# 02_I2C_V1-0.net
KiCad netlist of a schematic drawn in Altium Designer
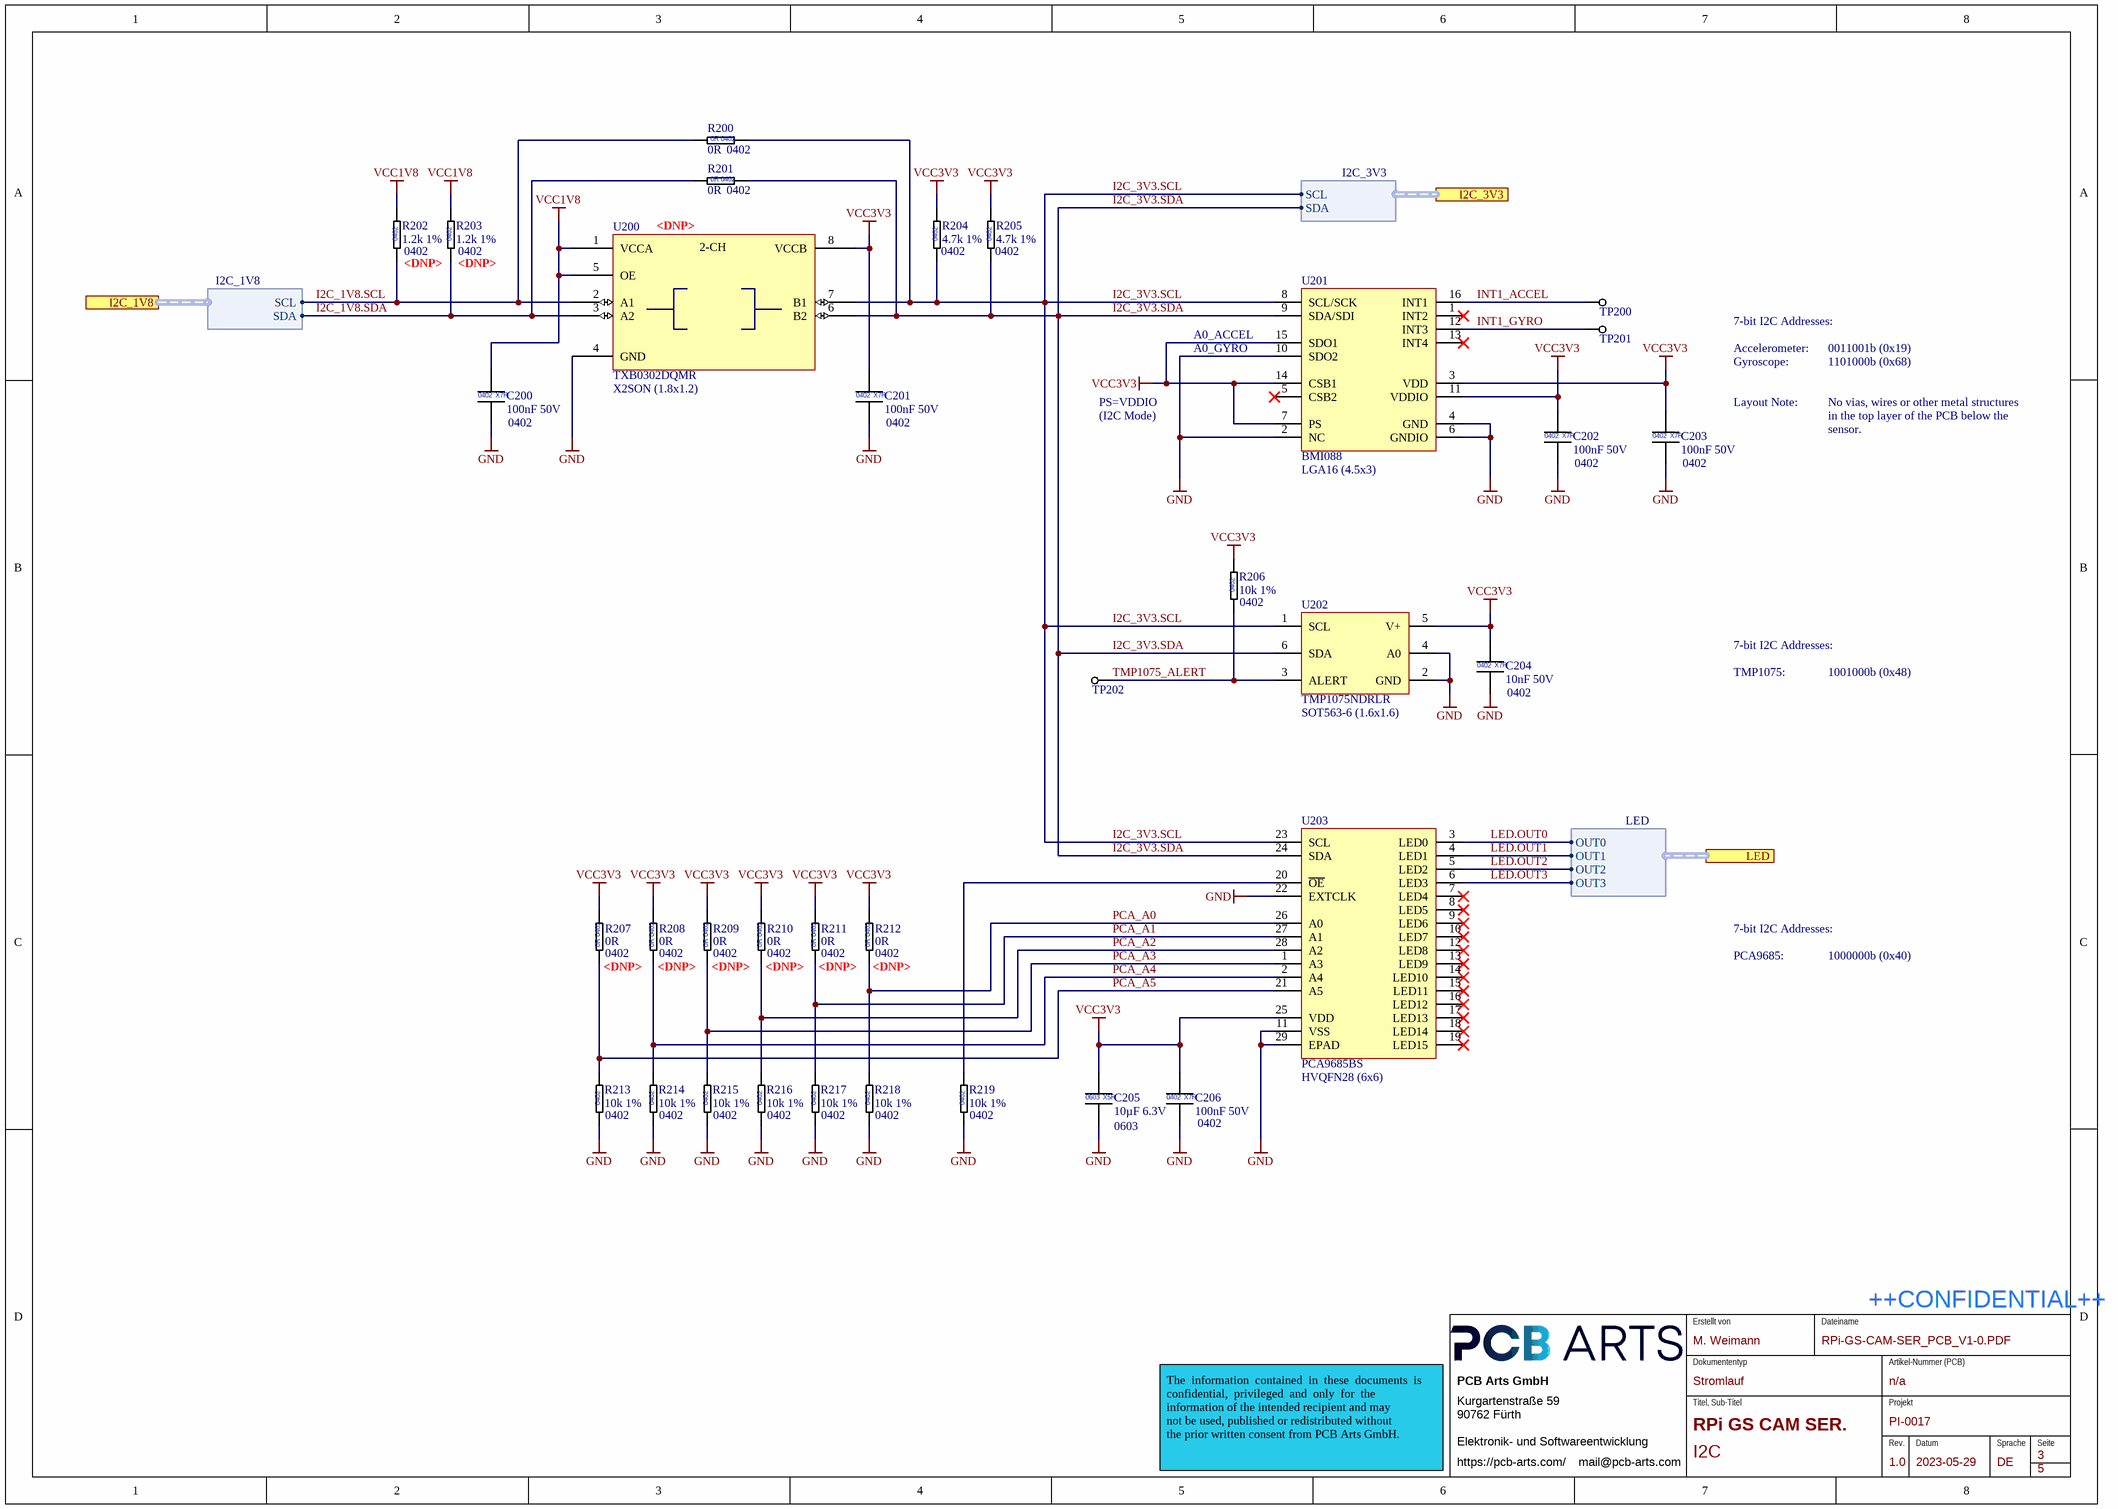
[diagram p0: 02_I2C_V1-0.SchDoc]

(export (version "E")
  (design (tool "Eeschema 10.0.6"))
  (components
    (comp (ref "C200")
      (value "100nF 50V")
      (footprint "Cap:CAP_0402_L")
      (description "Multilayer Ceramic Capacitors MLCC - SMD/SMT 0402 50VDC")
      (libsource (lib "Cap") (part "CAP_0402_100nF_50V"))
    )
    (comp (ref "C201")
      (value "100nF 50V")
      (footprint "Cap:CAP_0402_L")
      (description "Multilayer Ceramic Capacitors MLCC - SMD/SMT 0402 50VDC")
      (libsource (lib "Cap") (part "CAP_0402_100nF_50V"))
    )
    (comp (ref "C202")
      (value "100nF 50V")
      (footprint "Cap:CAP_0402_L")
      (description "Multilayer Ceramic Capacitors MLCC - SMD/SMT 0402 50VDC")
      (libsource (lib "Cap") (part "CAP_0402_100nF_50V"))
    )
    (comp (ref "C203")
      (value "100nF 50V")
      (footprint "Cap:CAP_0402_L")
      (description "Multilayer Ceramic Capacitors MLCC - SMD/SMT 0402 50VDC")
      (libsource (lib "Cap") (part "CAP_0402_100nF_50V"))
    )
    (comp (ref "C204")
      (value "10nF 50V")
      (footprint "Cap:CAP_0402_L")
      (description "Multilayer Ceramic Capacitors MLCC - SMD/SMT 0402 50VDC")
      (libsource (lib "Cap") (part "CAP_0402_10nF_50V"))
    )
    (comp (ref "C205")
      (value "10µF 6.3V")
      (footprint "Cap:CAP_0603_L")
      (description "Multilayer Ceramic Capacitors MLCC - SMD/SMT 0603 6.3VDC")
      (libsource (lib "Cap") (part "CAP_0603_10µF_6.3V"))
    )
    (comp (ref "C206")
      (value "100nF 50V")
      (footprint "Cap:CAP_0402_L")
      (description "Multilayer Ceramic Capacitors MLCC - SMD/SMT 0402 50VDC")
      (libsource (lib "Cap") (part "CAP_0402_100nF_50V"))
    )
    (comp (ref "R200")
      (value "0R Jumper")
      (footprint "Res:RES_0402_L")
      (description "Thick Film Resistors - SMD 0Ohm")
      (libsource (lib "Res") (part "RES_0402_0R Jumper"))
    )
    (comp (ref "R201")
      (value "0R Jumper")
      (footprint "Res:RES_0402_L")
      (description "Thick Film Resistors - SMD 0Ohm")
      (libsource (lib "Res") (part "RES_0402_0R Jumper"))
    )
    (comp (ref "R202")
      (value "1.2k 1%")
      (footprint "Res:RES_0402_L")
      (description "Thick Film Resistors - SMD 1/16watt 1.2Kohms 1%")
      (libsource (lib "Res") (part "RES_0402_1.2k_1%"))
    )
    (comp (ref "R203")
      (value "1.2k 1%")
      (footprint "Res:RES_0402_L")
      (description "Thick Film Resistors - SMD 1/16watt 1.2Kohms 1%")
      (libsource (lib "Res") (part "RES_0402_1.2k_1%"))
    )
    (comp (ref "R204")
      (value "4.7k 1%")
      (footprint "Res:RES_0402_L")
      (description "Thick Film Resistors - SMD 4.7kOhm 1%")
      (libsource (lib "Res") (part "RES_0402_4.7k_1%"))
    )
    (comp (ref "R205")
      (value "4.7k 1%")
      (footprint "Res:RES_0402_L")
      (description "Thick Film Resistors - SMD 4.7kOhm 1%")
      (libsource (lib "Res") (part "RES_0402_4.7k_1%"))
    )
    (comp (ref "R206")
      (value "10k 1%")
      (footprint "Res:RES_0402_L")
      (description "Thick Film Resistors - SMD 10kOhm 1%")
      (libsource (lib "Res") (part "RES_0402_10k_1%"))
    )
    (comp (ref "R207")
      (value "0R Jumper")
      (footprint "Res:RES_0402_L")
      (description "Thick Film Resistors - SMD 0Ohm")
      (libsource (lib "Res") (part "RES_0402_0R Jumper"))
    )
    (comp (ref "R208")
      (value "0R Jumper")
      (footprint "Res:RES_0402_L")
      (description "Thick Film Resistors - SMD 0Ohm")
      (libsource (lib "Res") (part "RES_0402_0R Jumper"))
    )
    (comp (ref "R209")
      (value "0R Jumper")
      (footprint "Res:RES_0402_L")
      (description "Thick Film Resistors - SMD 0Ohm")
      (libsource (lib "Res") (part "RES_0402_0R Jumper"))
    )
    (comp (ref "R210")
      (value "0R Jumper")
      (footprint "Res:RES_0402_L")
      (description "Thick Film Resistors - SMD 0Ohm")
      (libsource (lib "Res") (part "RES_0402_0R Jumper"))
    )
    (comp (ref "R211")
      (value "0R Jumper")
      (footprint "Res:RES_0402_L")
      (description "Thick Film Resistors - SMD 0Ohm")
      (libsource (lib "Res") (part "RES_0402_0R Jumper"))
    )
    (comp (ref "R212")
      (value "0R Jumper")
      (footprint "Res:RES_0402_L")
      (description "Thick Film Resistors - SMD 0Ohm")
      (libsource (lib "Res") (part "RES_0402_0R Jumper"))
    )
    (comp (ref "R213")
      (value "10k 1%")
      (footprint "Res:RES_0402_L")
      (description "Thick Film Resistors - SMD 10kOhm 1%")
      (libsource (lib "Res") (part "RES_0402_10k_1%"))
    )
    (comp (ref "R214")
      (value "10k 1%")
      (footprint "Res:RES_0402_L")
      (description "Thick Film Resistors - SMD 10kOhm 1%")
      (libsource (lib "Res") (part "RES_0402_10k_1%"))
    )
    (comp (ref "R215")
      (value "10k 1%")
      (footprint "Res:RES_0402_L")
      (description "Thick Film Resistors - SMD 10kOhm 1%")
      (libsource (lib "Res") (part "RES_0402_10k_1%"))
    )
    (comp (ref "R216")
      (value "10k 1%")
      (footprint "Res:RES_0402_L")
      (description "Thick Film Resistors - SMD 10kOhm 1%")
      (libsource (lib "Res") (part "RES_0402_10k_1%"))
    )
    (comp (ref "R217")
      (value "10k 1%")
      (footprint "Res:RES_0402_L")
      (description "Thick Film Resistors - SMD 10kOhm 1%")
      (libsource (lib "Res") (part "RES_0402_10k_1%"))
    )
    (comp (ref "R218")
      (value "10k 1%")
      (footprint "Res:RES_0402_L")
      (description "Thick Film Resistors - SMD 10kOhm 1%")
      (libsource (lib "Res") (part "RES_0402_10k_1%"))
    )
    (comp (ref "R219")
      (value "10k 1%")
      (footprint "Res:RES_0402_L")
      (description "Thick Film Resistors - SMD 10kOhm 1%")
      (libsource (lib "Res") (part "RES_0402_10k_1%"))
    )
    (comp (ref "TP200")
      (value "Testpoint")
      (footprint "Electro_mech:Testpoint 0.8mm")
      (description "Testpoint 0.8mm")
      (libsource (lib "Electro_Mech") (part "Testpoint 0.8mm"))
    )
    (comp (ref "TP201")
      (value "Testpoint")
      (footprint "Electro_mech:Testpoint 0.8mm")
      (description "Testpoint 0.8mm")
      (libsource (lib "Electro_Mech") (part "Testpoint 0.8mm"))
    )
    (comp (ref "TP202")
      (value "Testpoint")
      (footprint "Electro_mech:Testpoint 0.8mm")
      (description "Testpoint 0.8mm")
      (libsource (lib "Electro_Mech") (part "Testpoint 0.8mm"))
    )
    (comp (ref "U200")
      (value "TXB0302DQMR")
      (footprint "Digital:SON40P120X40-8N")
      (description "Translation - Voltage Levels 2B Bidir Vltg-Level Translator")
      (libsource (lib "Digital") (part "TXB0302DQMR_Translation - Voltage Levels 2B Bidir Vltg-Level Translator"))
    )
    (comp (ref "U201")
      (value "BMI088")
      (footprint "LGA50P450X300X100-16N")
      (libsource (lib "Digital") (part "BMI088_High_Performance_Intertial_Measurement_Unit_(IMU)"))
    )
    (comp (ref "U202")
      (value "TMP1075NDRLR")
      (footprint "SOT50P160X60-6N_SOT563")
      (libsource (lib "Digital") (part "TMP1075NDRLR_Board_Mount_I2C_Temperature_Sensor"))
    )
    (comp (ref "U203")
      (value "PCA9685BS")
      (footprint "QFN65P600X600X100_HS-29N")
      (description "LED-Anzeigetreiber 16-CH 12-BIT PWM FM+ I2C-BUS LED CTRL HVQFN28 6 mm x 6 mm")
      (libsource (lib "Digital") (part "PCA9685BS_16-CH_12-BIT-PWM_I2C_LED-CTRL"))
    )
  )
  (nets
    (net (code "4") (name "/I2C_1V8.SCL") (class "Default")
      (node (ref "R200") (pin "1") (pinfunction "1_1") (pintype "passive"))
      (node (ref "R202") (pin "1") (pinfunction "1_1") (pintype "passive"))
      (node (ref "U200") (pin "2") (pinfunction "A1_2") (pintype "bidirectional"))
    )
    (net (code "5") (name "/I2C_1V8.SDA") (class "Default")
      (node (ref "R201") (pin "1") (pinfunction "1_1") (pintype "passive"))
      (node (ref "R203") (pin "1") (pinfunction "1_1") (pintype "passive"))
      (node (ref "U200") (pin "3") (pinfunction "A2_3") (pintype "bidirectional"))
    )
    (net (code "6") (name "/I2C_3V3.SCL") (class "Default")
      (node (ref "R200") (pin "2") (pinfunction "2_2") (pintype "passive"))
      (node (ref "R204") (pin "1") (pinfunction "1_1") (pintype "passive"))
      (node (ref "U200") (pin "7") (pinfunction "B1_7") (pintype "bidirectional"))
      (node (ref "U201") (pin "8") (pinfunction "SCL/SCK_8") (pintype "passive"))
      (node (ref "U202") (pin "1") (pinfunction "SCL_1") (pintype "passive"))
      (node (ref "U203") (pin "23") (pinfunction "SCL_23") (pintype "passive"))
    )
    (net (code "7") (name "/I2C_3V3.SDA") (class "Default")
      (node (ref "R201") (pin "2") (pinfunction "2_2") (pintype "passive"))
      (node (ref "R205") (pin "1") (pinfunction "1_1") (pintype "passive"))
      (node (ref "U200") (pin "6") (pinfunction "B2_6") (pintype "bidirectional"))
      (node (ref "U201") (pin "9") (pinfunction "SDA/SDI_9") (pintype "passive"))
      (node (ref "U202") (pin "6") (pinfunction "SDA_6") (pintype "passive"))
      (node (ref "U203") (pin "24") (pinfunction "SDA_24") (pintype "passive"))
    )
    (net (code "8") (name "/INT1_ACCEL") (class "Default")
      (node (ref "TP200") (pin "1") (pinfunction "GND_1") (pintype "passive"))
      (node (ref "U201") (pin "16") (pinfunction "INT1_16") (pintype "passive"))
    )
    (net (code "9") (name "/INT1_GYRO") (class "Default")
      (node (ref "TP201") (pin "1") (pinfunction "GND_1") (pintype "passive"))
      (node (ref "U201") (pin "12") (pinfunction "INT3_12") (pintype "passive"))
    )
    (net (code "10") (name "/LED.OUT0") (class "Default")
      (node (ref "U203") (pin "3") (pinfunction "LED0_3") (pintype "passive"))
    )
    (net (code "11") (name "/LED.OUT1") (class "Default")
      (node (ref "U203") (pin "4") (pinfunction "LED1_4") (pintype "passive"))
    )
    (net (code "12") (name "/LED.OUT2") (class "Default")
      (node (ref "U203") (pin "5") (pinfunction "LED2_5") (pintype "passive"))
    )
    (net (code "13") (name "/LED.OUT3") (class "Default")
      (node (ref "U203") (pin "6") (pinfunction "LED3_6") (pintype "passive"))
    )
    (net (code "14") (name "/PCA_A0") (class "Default")
      (node (ref "R212") (pin "1") (pinfunction "1_1") (pintype "passive"))
      (node (ref "R218") (pin "2") (pinfunction "2_2") (pintype "passive"))
      (node (ref "U203") (pin "26") (pinfunction "A0_26") (pintype "passive"))
    )
    (net (code "15") (name "/PCA_A1") (class "Default")
      (node (ref "R211") (pin "1") (pinfunction "1_1") (pintype "passive"))
      (node (ref "R217") (pin "2") (pinfunction "2_2") (pintype "passive"))
      (node (ref "U203") (pin "27") (pinfunction "A1_27") (pintype "passive"))
    )
    (net (code "16") (name "/PCA_A2") (class "Default")
      (node (ref "R210") (pin "1") (pinfunction "1_1") (pintype "passive"))
      (node (ref "R216") (pin "2") (pinfunction "2_2") (pintype "passive"))
      (node (ref "U203") (pin "28") (pinfunction "A2_28") (pintype "passive"))
    )
    (net (code "17") (name "/PCA_A3") (class "Default")
      (node (ref "R209") (pin "1") (pinfunction "1_1") (pintype "passive"))
      (node (ref "R215") (pin "2") (pinfunction "2_2") (pintype "passive"))
      (node (ref "U203") (pin "1") (pinfunction "A3_1") (pintype "passive"))
    )
    (net (code "18") (name "/PCA_A4") (class "Default")
      (node (ref "R208") (pin "1") (pinfunction "1_1") (pintype "passive"))
      (node (ref "R214") (pin "2") (pinfunction "2_2") (pintype "passive"))
      (node (ref "U203") (pin "2") (pinfunction "A4_2") (pintype "passive"))
    )
    (net (code "19") (name "/PCA_A5") (class "Default")
      (node (ref "R207") (pin "1") (pinfunction "1_1") (pintype "passive"))
      (node (ref "R213") (pin "2") (pinfunction "2_2") (pintype "passive"))
      (node (ref "U203") (pin "21") (pinfunction "A5_21") (pintype "passive"))
    )
    (net (code "20") (name "/TMP1075_ALERT") (class "Default")
      (node (ref "R206") (pin "1") (pinfunction "1_1") (pintype "passive"))
      (node (ref "TP202") (pin "1") (pinfunction "GND_1") (pintype "passive"))
      (node (ref "U202") (pin "3") (pinfunction "ALERT_3") (pintype "passive"))
    )
    (net (code "24") (name "GND") (class "Default")
      (node (ref "C200") (pin "2") (pinfunction "2_2") (pintype "passive"))
      (node (ref "C201") (pin "2") (pinfunction "2_2") (pintype "passive"))
      (node (ref "C202") (pin "2") (pinfunction "2_2") (pintype "passive"))
      (node (ref "C203") (pin "2") (pinfunction "2_2") (pintype "passive"))
      (node (ref "C204") (pin "2") (pinfunction "2_2") (pintype "passive"))
      (node (ref "C205") (pin "2") (pinfunction "2_2") (pintype "passive"))
      (node (ref "C206") (pin "2") (pinfunction "2_2") (pintype "passive"))
      (node (ref "R213") (pin "1") (pinfunction "1_1") (pintype "passive"))
      (node (ref "R214") (pin "1") (pinfunction "1_1") (pintype "passive"))
      (node (ref "R215") (pin "1") (pinfunction "1_1") (pintype "passive"))
      (node (ref "R216") (pin "1") (pinfunction "1_1") (pintype "passive"))
      (node (ref "R217") (pin "1") (pinfunction "1_1") (pintype "passive"))
      (node (ref "R218") (pin "1") (pinfunction "1_1") (pintype "passive"))
      (node (ref "R219") (pin "1") (pinfunction "1_1") (pintype "passive"))
      (node (ref "U200") (pin "4") (pinfunction "GND_4") (pintype "power_in"))
      (node (ref "U201") (pin "10") (pinfunction "SDO2_10") (pintype "passive"))
      (node (ref "U201") (pin "2") (pinfunction "NC_2") (pintype "passive"))
      (node (ref "U201") (pin "4") (pinfunction "GND_4") (pintype "passive"))
      (node (ref "U201") (pin "6") (pinfunction "GNDIO_6") (pintype "passive"))
      (node (ref "U202") (pin "2") (pinfunction "GND_2") (pintype "passive"))
      (node (ref "U202") (pin "4") (pinfunction "A0_4") (pintype "passive"))
      (node (ref "U203") (pin "11") (pinfunction "VSS_11") (pintype "passive"))
      (node (ref "U203") (pin "22") (pinfunction "EXTCLK_22") (pintype "passive"))
      (node (ref "U203") (pin "29") (pinfunction "EPAD_29") (pintype "passive"))
    )
    (net (code "25") (name "Net-(U203-~{OE})") (class "Default")
      (node (ref "R219") (pin "2") (pinfunction "2_2") (pintype "passive"))
      (node (ref "U203") (pin "20") (pinfunction "~{OE}_20") (pintype "passive"))
    )
    (net (code "26") (name "VCC1V8") (class "Default")
      (node (ref "C200") (pin "1") (pinfunction "1_1") (pintype "passive"))
      (node (ref "R202") (pin "2") (pinfunction "2_2") (pintype "passive"))
      (node (ref "R203") (pin "2") (pinfunction "2_2") (pintype "passive"))
      (node (ref "U200") (pin "1") (pinfunction "VCCA_1") (pintype "power_in"))
      (node (ref "U200") (pin "5") (pinfunction "OE_5") (pintype "power_in"))
    )
    (net (code "27") (name "VCC3V3") (class "Default")
      (node (ref "C201") (pin "1") (pinfunction "1_1") (pintype "passive"))
      (node (ref "C202") (pin "1") (pinfunction "1_1") (pintype "passive"))
      (node (ref "C203") (pin "1") (pinfunction "1_1") (pintype "passive"))
      (node (ref "C204") (pin "1") (pinfunction "1_1") (pintype "passive"))
      (node (ref "C205") (pin "1") (pinfunction "1_1") (pintype "passive"))
      (node (ref "C206") (pin "1") (pinfunction "1_1") (pintype "passive"))
      (node (ref "R204") (pin "2") (pinfunction "2_2") (pintype "passive"))
      (node (ref "R205") (pin "2") (pinfunction "2_2") (pintype "passive"))
      (node (ref "R206") (pin "2") (pinfunction "2_2") (pintype "passive"))
      (node (ref "R207") (pin "2") (pinfunction "2_2") (pintype "passive"))
      (node (ref "R208") (pin "2") (pinfunction "2_2") (pintype "passive"))
      (node (ref "R209") (pin "2") (pinfunction "2_2") (pintype "passive"))
      (node (ref "R210") (pin "2") (pinfunction "2_2") (pintype "passive"))
      (node (ref "R211") (pin "2") (pinfunction "2_2") (pintype "passive"))
      (node (ref "R212") (pin "2") (pinfunction "2_2") (pintype "passive"))
      (node (ref "U200") (pin "8") (pinfunction "VCCB_8") (pintype "power_in"))
      (node (ref "U201") (pin "11") (pinfunction "VDDIO_11") (pintype "passive"))
      (node (ref "U201") (pin "14") (pinfunction "CSB1_14") (pintype "passive"))
      (node (ref "U201") (pin "15") (pinfunction "SDO1_15") (pintype "passive"))
      (node (ref "U201") (pin "3") (pinfunction "VDD_3") (pintype "passive"))
      (node (ref "U201") (pin "7") (pinfunction "PS_7") (pintype "passive"))
      (node (ref "U202") (pin "5") (pinfunction "V+_5") (pintype "passive"))
      (node (ref "U203") (pin "25") (pinfunction "VDD_25") (pintype "passive"))
    )
    (net (code "28") (name "unconnected-(U201-CSB2-Pad5)") (class "Default")
      (node (ref "U201") (pin "5") (pinfunction "CSB2_5") (pintype "passive+no_connect"))
    )
    (net (code "29") (name "unconnected-(U201-INT2-Pad1)") (class "Default")
      (node (ref "U201") (pin "1") (pinfunction "INT2_1") (pintype "passive+no_connect"))
    )
    (net (code "30") (name "unconnected-(U201-INT4-Pad13)") (class "Default")
      (node (ref "U201") (pin "13") (pinfunction "INT4_13") (pintype "passive+no_connect"))
    )
    (net (code "31") (name "unconnected-(U203-LED4-Pad7)") (class "Default")
      (node (ref "U203") (pin "7") (pinfunction "LED4_7") (pintype "passive+no_connect"))
    )
    (net (code "32") (name "unconnected-(U203-LED5-Pad8)") (class "Default")
      (node (ref "U203") (pin "8") (pinfunction "LED5_8") (pintype "passive+no_connect"))
    )
    (net (code "33") (name "unconnected-(U203-LED6-Pad9)") (class "Default")
      (node (ref "U203") (pin "9") (pinfunction "LED6_9") (pintype "passive+no_connect"))
    )
    (net (code "34") (name "unconnected-(U203-LED7-Pad10)") (class "Default")
      (node (ref "U203") (pin "10") (pinfunction "LED7_10") (pintype "passive+no_connect"))
    )
    (net (code "35") (name "unconnected-(U203-LED8-Pad12)") (class "Default")
      (node (ref "U203") (pin "12") (pinfunction "LED8_12") (pintype "passive+no_connect"))
    )
    (net (code "36") (name "unconnected-(U203-LED9-Pad13)") (class "Default")
      (node (ref "U203") (pin "13") (pinfunction "LED9_13") (pintype "passive+no_connect"))
    )
    (net (code "37") (name "unconnected-(U203-LED10-Pad14)") (class "Default")
      (node (ref "U203") (pin "14") (pinfunction "LED10_14") (pintype "passive+no_connect"))
    )
    (net (code "38") (name "unconnected-(U203-LED11-Pad15)") (class "Default")
      (node (ref "U203") (pin "15") (pinfunction "LED11_15") (pintype "passive+no_connect"))
    )
    (net (code "39") (name "unconnected-(U203-LED12-Pad16)") (class "Default")
      (node (ref "U203") (pin "16") (pinfunction "LED12_16") (pintype "passive+no_connect"))
    )
    (net (code "40") (name "unconnected-(U203-LED13-Pad17)") (class "Default")
      (node (ref "U203") (pin "17") (pinfunction "LED13_17") (pintype "passive+no_connect"))
    )
    (net (code "41") (name "unconnected-(U203-LED14-Pad18)") (class "Default")
      (node (ref "U203") (pin "18") (pinfunction "LED14_18") (pintype "passive+no_connect"))
    )
    (net (code "42") (name "unconnected-(U203-LED15-Pad19)") (class "Default")
      (node (ref "U203") (pin "19") (pinfunction "LED15_19") (pintype "passive+no_connect"))
    )
  )
)
